# hid.net
KiCad netlist of a schematic drawn in EAGLE
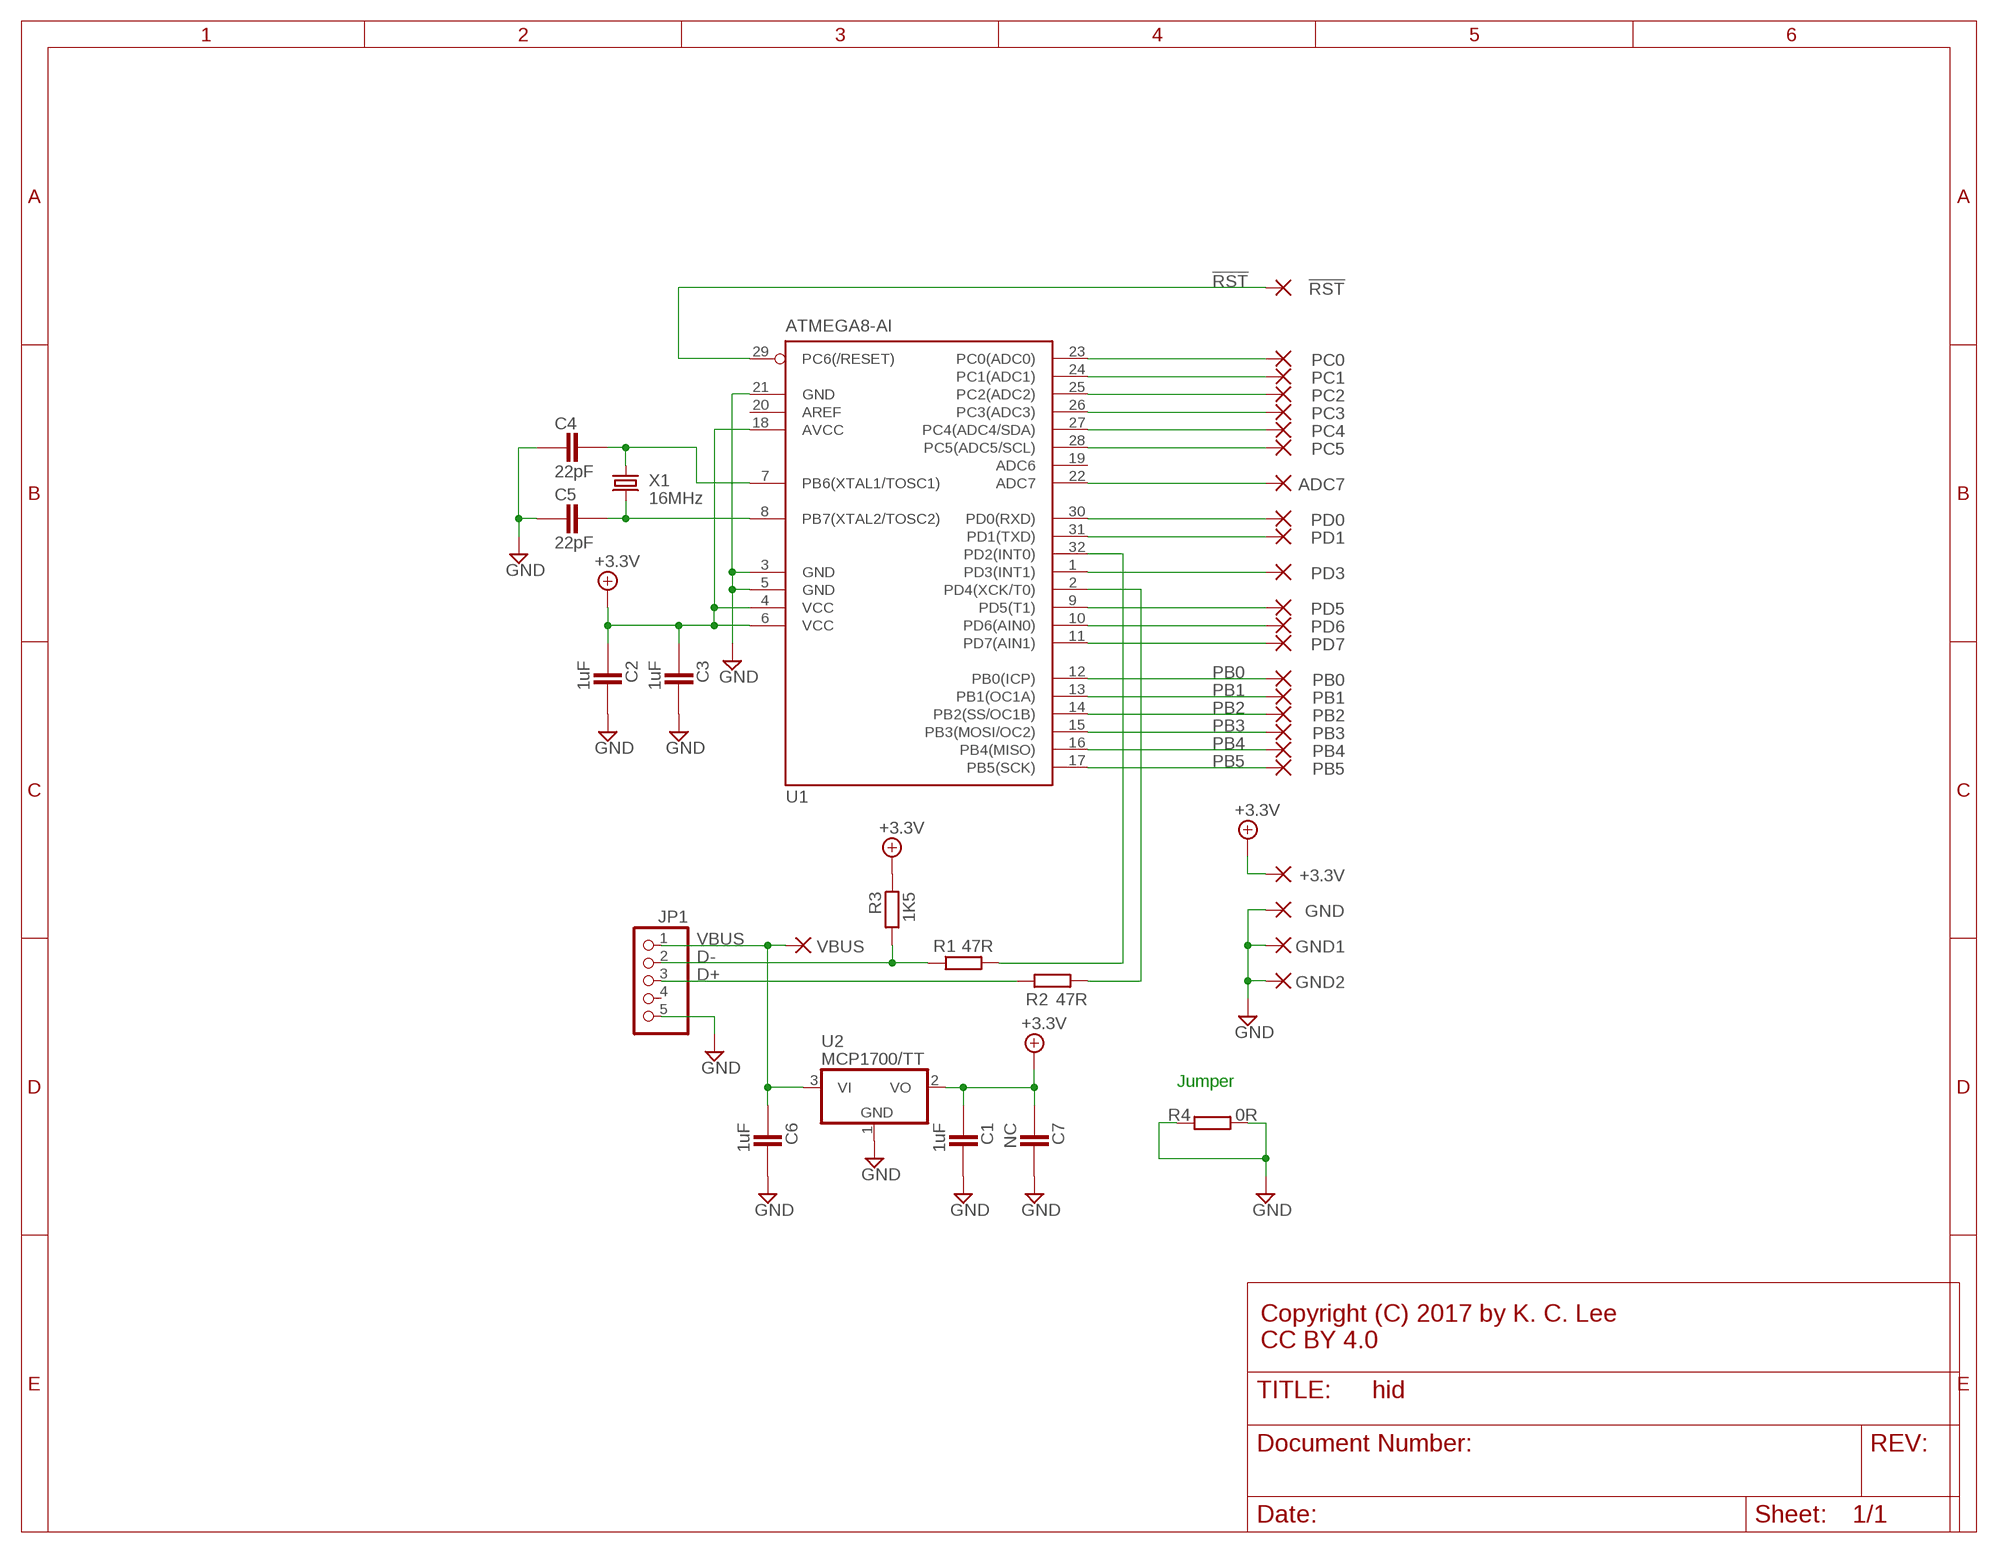
[diagram p0: schematic, sheet 1]

(export (version "E")
  (design (tool "Eeschema 10.0.6"))
  (components
    (comp (ref "!RST")
      (value "SMD2")
      (footprint "eagle-import:SMD1,27-2,54")
      (fields (field (name "PARTNO") "Breakout"))
      (libsource (lib "eagle-import") (part "SMD2"))
    )
    (comp (ref "+3.3V")
      (value "SMD2")
      (footprint "eagle-import:SMD1,27-2,54")
      (fields (field (name "PARTNO") "Breakout"))
      (libsource (lib "eagle-import") (part "SMD2"))
    )
    (comp (ref "ADC7")
      (value "SMD2")
      (footprint "eagle-import:SMD1,27-2,54")
      (fields (field (name "PARTNO") "Breakout"))
      (libsource (lib "eagle-import") (part "SMD2"))
    )
    (comp (ref "C1")
      (value "1uF")
      (footprint "eagle-import:CAPC1608X92N")
      (fields (field (name "PARTNO") "1uF X7R 0603"))
      (libsource (lib "eagle-import") (part "CAPACITOR_0603"))
    )
    (comp (ref "C2")
      (value "1uF")
      (footprint "eagle-import:CAPC1608X92N")
      (fields (field (name "PARTNO") "1uF X7R 0603"))
      (libsource (lib "eagle-import") (part "CAPACITOR_0603"))
    )
    (comp (ref "C3")
      (value "1uF")
      (footprint "eagle-import:CAPC1608X92N")
      (fields (field (name "PARTNO") "1uF X7R 0603"))
      (libsource (lib "eagle-import") (part "CAPACITOR_0603"))
    )
    (comp (ref "C4")
      (value "22pF")
      (footprint "eagle-import:CAPC1608X92N")
      (fields (field (name "PARTNO") "22pF 0603"))
      (libsource (lib "eagle-import") (part "CAPACITOR_0603"))
    )
    (comp (ref "C5")
      (value "22pF")
      (footprint "eagle-import:CAPC1608X92N")
      (fields (field (name "PARTNO") "22pF 0603"))
      (libsource (lib "eagle-import") (part "CAPACITOR_0603"))
    )
    (comp (ref "C6")
      (value "1uF")
      (footprint "eagle-import:CAPC1608X92N")
      (fields (field (name "PARTNO") "1uF X7R 0603"))
      (libsource (lib "eagle-import") (part "CAPACITOR_0603"))
    )
    (comp (ref "C7")
      (value "NC")
      (footprint "eagle-import:CAPC2012X145AN")
      (fields (field (name "PARTNO") "NC 0805"))
      (libsource (lib "eagle-import") (part "CAPACITOR_0805"))
    )
    (comp (ref "GND")
      (value "SMD2")
      (footprint "eagle-import:SMD1,27-2,54")
      (fields (field (name "PARTNO") "Breakout"))
      (libsource (lib "eagle-import") (part "SMD2"))
    )
    (comp (ref "GND1")
      (value "SMD2")
      (footprint "eagle-import:SMD1,27-2,54")
      (fields (field (name "PARTNO") "Breakout"))
      (libsource (lib "eagle-import") (part "SMD2"))
    )
    (comp (ref "GND2")
      (value "SMD2")
      (footprint "eagle-import:SMD1,27-2,54")
      (fields (field (name "PARTNO") "Breakout"))
      (libsource (lib "eagle-import") (part "SMD2"))
    )
    (comp (ref "JP1")
      (value "PINHD-1X5_2.54")
      (footprint "eagle-import:1X05")
      (libsource (lib "eagle-import") (part "PINHD-1X5_2.54"))
    )
    (comp (ref "PB0")
      (value "SMD2")
      (footprint "eagle-import:SMD1,27-2,54")
      (fields (field (name "PARTNO") "Breakout"))
      (libsource (lib "eagle-import") (part "SMD2"))
    )
    (comp (ref "PB1")
      (value "SMD2")
      (footprint "eagle-import:SMD1,27-2,54")
      (fields (field (name "PARTNO") "Breakout"))
      (libsource (lib "eagle-import") (part "SMD2"))
    )
    (comp (ref "PB2")
      (value "SMD2")
      (footprint "eagle-import:SMD1,27-2,54")
      (fields (field (name "PARTNO") "Breakout"))
      (libsource (lib "eagle-import") (part "SMD2"))
    )
    (comp (ref "PB3")
      (value "SMD2")
      (footprint "eagle-import:SMD1,27-2,54")
      (fields (field (name "PARTNO") "Breakout"))
      (libsource (lib "eagle-import") (part "SMD2"))
    )
    (comp (ref "PB4")
      (value "SMD2")
      (footprint "eagle-import:SMD1,27-2,54")
      (fields (field (name "PARTNO") "Breakout"))
      (libsource (lib "eagle-import") (part "SMD2"))
    )
    (comp (ref "PB5")
      (value "SMD2")
      (footprint "eagle-import:SMD1,27-2,54")
      (fields (field (name "PARTNO") "Breakout"))
      (libsource (lib "eagle-import") (part "SMD2"))
    )
    (comp (ref "PC0")
      (value "SMD2")
      (footprint "eagle-import:SMD1,27-2,54")
      (fields (field (name "PARTNO") "Breakout"))
      (libsource (lib "eagle-import") (part "SMD2"))
    )
    (comp (ref "PC1")
      (value "SMD2")
      (footprint "eagle-import:SMD1,27-2,54")
      (fields (field (name "PARTNO") "Breakout"))
      (libsource (lib "eagle-import") (part "SMD2"))
    )
    (comp (ref "PC2")
      (value "SMD2")
      (footprint "eagle-import:SMD1,27-2,54")
      (fields (field (name "PARTNO") "Breakout"))
      (libsource (lib "eagle-import") (part "SMD2"))
    )
    (comp (ref "PC3")
      (value "SMD2")
      (footprint "eagle-import:SMD1,27-2,54")
      (fields (field (name "PARTNO") "Breakout"))
      (libsource (lib "eagle-import") (part "SMD2"))
    )
    (comp (ref "PC4")
      (value "SMD2")
      (footprint "eagle-import:SMD1,27-2,54")
      (fields (field (name "PARTNO") "Breakout"))
      (libsource (lib "eagle-import") (part "SMD2"))
    )
    (comp (ref "PC5")
      (value "SMD2")
      (footprint "eagle-import:SMD1,27-2,54")
      (fields (field (name "PARTNO") "Breakout"))
      (libsource (lib "eagle-import") (part "SMD2"))
    )
    (comp (ref "PD0")
      (value "SMD2")
      (footprint "eagle-import:SMD1,27-2,54")
      (fields (field (name "PARTNO") "Breakout"))
      (libsource (lib "eagle-import") (part "SMD2"))
    )
    (comp (ref "PD1")
      (value "SMD2")
      (footprint "eagle-import:SMD1,27-2,54")
      (fields (field (name "PARTNO") "Breakout"))
      (libsource (lib "eagle-import") (part "SMD2"))
    )
    (comp (ref "PD3")
      (value "SMD2")
      (footprint "eagle-import:SMD1,27-2,54")
      (fields (field (name "PARTNO") "Breakout"))
      (libsource (lib "eagle-import") (part "SMD2"))
    )
    (comp (ref "PD5")
      (value "SMD2")
      (footprint "eagle-import:SMD1,27-2,54")
      (fields (field (name "PARTNO") "Breakout"))
      (libsource (lib "eagle-import") (part "SMD2"))
    )
    (comp (ref "PD6")
      (value "SMD2")
      (footprint "eagle-import:SMD1,27-2,54")
      (fields (field (name "PARTNO") "Breakout"))
      (libsource (lib "eagle-import") (part "SMD2"))
    )
    (comp (ref "PD7")
      (value "SMD2")
      (footprint "eagle-import:SMD1,27-2,54")
      (fields (field (name "PARTNO") "Breakout"))
      (libsource (lib "eagle-import") (part "SMD2"))
    )
    (comp (ref "R1")
      (value "47R")
      (footprint "eagle-import:RESC1608X55N")
      (fields (field (name "PARTNO") "47R 0603"))
      (libsource (lib "eagle-import") (part "RESISTOR_0603"))
    )
    (comp (ref "R2")
      (value "47R")
      (footprint "eagle-import:RESC1608X55N")
      (fields (field (name "PARTNO") "47R 0603"))
      (libsource (lib "eagle-import") (part "RESISTOR_0603"))
    )
    (comp (ref "R3")
      (value "1K5")
      (footprint "eagle-import:RESC1608X55N")
      (fields (field (name "PARTNO") "1K5 0603"))
      (libsource (lib "eagle-import") (part "RESISTOR_0603"))
    )
    (comp (ref "R4")
      (value "0R")
      (footprint "eagle-import:RESC3115X70N")
      (fields (field (name "PARTNO") "0R 1206"))
      (libsource (lib "eagle-import") (part "RESISTOR_1206"))
    )
    (comp (ref "U1")
      (value "ATMEGA8-AI")
      (footprint "eagle-import:TQFP32-08")
      (fields (field (name "PARTNO") "ATmega8A-AU"))
      (libsource (lib "eagle-import") (part "MEGA8-AI"))
    )
    (comp (ref "U2")
      (value "MCP1700/TT")
      (footprint "eagle-import:SOT95P280X135-3N")
      (fields (field (name "PARTNO") "MCP1700T-3302E/TT"))
      (libsource (lib "eagle-import") (part "MCP1700/TT"))
    )
    (comp (ref "VBUS")
      (value "SMD2")
      (footprint "eagle-import:SMD1,27-2,54")
      (fields (field (name "PARTNO") "Breakout"))
      (libsource (lib "eagle-import") (part "SMD2"))
    )
    (comp (ref "X1")
      (value "16MHz")
      (footprint "eagle-import:TC26H")
      (fields (field (name "PARTNO") "16MHz Crystal TC26"))
      (libsource (lib "eagle-import") (part "CRYSTALTC26H"))
    )
  )
  (nets
    (net (code "1") (name "+3.3V") (class "Default")
      (node (ref "+3.3V") (pin "1") (pinfunction "P_1") (pintype "passive"))
      (node (ref "C1") (pin "1") (pinfunction "1_1") (pintype "passive"))
      (node (ref "C2") (pin "1") (pinfunction "1_1") (pintype "passive"))
      (node (ref "C3") (pin "1") (pinfunction "1_1") (pintype "passive"))
      (node (ref "C7") (pin "1") (pinfunction "1_1") (pintype "passive"))
      (node (ref "R3") (pin "1") (pinfunction "1_1") (pintype "passive"))
      (node (ref "U1") (pin "18") (pinfunction "AVCC_18") (pintype "power_in"))
      (node (ref "U1") (pin "4") (pinfunction "VCC_4") (pintype "power_in"))
      (node (ref "U1") (pin "6") (pinfunction "VCC_6") (pintype "power_in"))
      (node (ref "U2") (pin "2") (pinfunction "VO_2") (pintype "passive"))
    )
    (net (code "2") (name "/D+") (class "Default")
      (node (ref "JP1") (pin "3") (pinfunction "3_3") (pintype "passive"))
      (node (ref "R2") (pin "1") (pinfunction "1_1") (pintype "passive"))
    )
    (net (code "3") (name "/D-") (class "Default")
      (node (ref "JP1") (pin "2") (pinfunction "2_2") (pintype "passive"))
      (node (ref "R1") (pin "1") (pinfunction "1_1") (pintype "passive"))
      (node (ref "R3") (pin "2") (pinfunction "2_2") (pintype "passive"))
    )
    (net (code "4") (name "/PB0") (class "Default")
      (node (ref "PB0") (pin "1") (pinfunction "P_1") (pintype "passive"))
      (node (ref "U1") (pin "12") (pinfunction "PB0(ICP)_12") (pintype "bidirectional"))
    )
    (net (code "5") (name "/PB1") (class "Default")
      (node (ref "PB1") (pin "1") (pinfunction "P_1") (pintype "passive"))
      (node (ref "U1") (pin "13") (pinfunction "PB1(OC1A)_13") (pintype "bidirectional"))
    )
    (net (code "6") (name "/PB2") (class "Default")
      (node (ref "PB2") (pin "1") (pinfunction "P_1") (pintype "passive"))
      (node (ref "U1") (pin "14") (pinfunction "PB2(SS/OC1B)_14") (pintype "bidirectional"))
    )
    (net (code "7") (name "/PB3") (class "Default")
      (node (ref "PB3") (pin "1") (pinfunction "P_1") (pintype "passive"))
      (node (ref "U1") (pin "15") (pinfunction "PB3(MOSI/OC2)_15") (pintype "bidirectional"))
    )
    (net (code "8") (name "/PB4") (class "Default")
      (node (ref "PB4") (pin "1") (pinfunction "P_1") (pintype "passive"))
      (node (ref "U1") (pin "16") (pinfunction "PB4(MISO)_16") (pintype "bidirectional"))
    )
    (net (code "9") (name "/PB5") (class "Default")
      (node (ref "PB5") (pin "1") (pinfunction "P_1") (pintype "passive"))
      (node (ref "U1") (pin "17") (pinfunction "PB5(SCK)_17") (pintype "bidirectional"))
    )
    (net (code "10") (name "/VBUS") (class "Default")
      (node (ref "C6") (pin "1") (pinfunction "1_1") (pintype "passive"))
      (node (ref "JP1") (pin "1") (pinfunction "1_1") (pintype "passive"))
      (node (ref "U2") (pin "3") (pinfunction "VI_3") (pintype "input"))
      (node (ref "VBUS") (pin "1") (pinfunction "P_1") (pintype "passive"))
    )
    (net (code "11") (name "/~{RST}") (class "Default")
      (node (ref "!RST") (pin "1") (pinfunction "P_1") (pintype "passive"))
      (node (ref "U1") (pin "29") (pinfunction "PC6(/RESET)_29") (pintype "bidirectional"))
    )
    (net (code "12") (name "GND") (class "Default")
      (node (ref "C1") (pin "2") (pinfunction "2_2") (pintype "passive"))
      (node (ref "C2") (pin "2") (pinfunction "2_2") (pintype "passive"))
      (node (ref "C3") (pin "2") (pinfunction "2_2") (pintype "passive"))
      (node (ref "C4") (pin "1") (pinfunction "1_1") (pintype "passive"))
      (node (ref "C5") (pin "1") (pinfunction "1_1") (pintype "passive"))
      (node (ref "C6") (pin "2") (pinfunction "2_2") (pintype "passive"))
      (node (ref "C7") (pin "2") (pinfunction "2_2") (pintype "passive"))
      (node (ref "GND") (pin "1") (pinfunction "P_1") (pintype "passive"))
      (node (ref "GND1") (pin "1") (pinfunction "P_1") (pintype "passive"))
      (node (ref "GND2") (pin "1") (pinfunction "P_1") (pintype "passive"))
      (node (ref "JP1") (pin "5") (pinfunction "5_5") (pintype "passive"))
      (node (ref "R4") (pin "1") (pinfunction "1_1") (pintype "passive"))
      (node (ref "R4") (pin "2") (pinfunction "2_2") (pintype "passive"))
      (node (ref "U1") (pin "21") (pinfunction "GND_21") (pintype "power_in"))
      (node (ref "U1") (pin "3") (pinfunction "GND_3") (pintype "power_in"))
      (node (ref "U1") (pin "5") (pinfunction "GND_5") (pintype "power_in"))
      (node (ref "U2") (pin "1") (pinfunction "GND_1") (pintype "passive"))
    )
    (net (code "13") (name "Net-(ADC7-P)") (class "Default")
      (node (ref "ADC7") (pin "1") (pinfunction "P_1") (pintype "passive"))
      (node (ref "U1") (pin "22") (pinfunction "ADC7_22") (pintype "bidirectional"))
    )
    (net (code "14") (name "Net-(PC0-P)") (class "Default")
      (node (ref "PC0") (pin "1") (pinfunction "P_1") (pintype "passive"))
      (node (ref "U1") (pin "23") (pinfunction "PC0(ADC0)_23") (pintype "bidirectional"))
    )
    (net (code "15") (name "Net-(PC1-P)") (class "Default")
      (node (ref "PC1") (pin "1") (pinfunction "P_1") (pintype "passive"))
      (node (ref "U1") (pin "24") (pinfunction "PC1(ADC1)_24") (pintype "bidirectional"))
    )
    (net (code "16") (name "Net-(PC2-P)") (class "Default")
      (node (ref "PC2") (pin "1") (pinfunction "P_1") (pintype "passive"))
      (node (ref "U1") (pin "25") (pinfunction "PC2(ADC2)_25") (pintype "bidirectional"))
    )
    (net (code "17") (name "Net-(PC3-P)") (class "Default")
      (node (ref "PC3") (pin "1") (pinfunction "P_1") (pintype "passive"))
      (node (ref "U1") (pin "26") (pinfunction "PC3(ADC3)_26") (pintype "bidirectional"))
    )
    (net (code "18") (name "Net-(PC4-P)") (class "Default")
      (node (ref "PC4") (pin "1") (pinfunction "P_1") (pintype "passive"))
      (node (ref "U1") (pin "27") (pinfunction "PC4(ADC4/SDA)_27") (pintype "bidirectional"))
    )
    (net (code "19") (name "Net-(PC5-P)") (class "Default")
      (node (ref "PC5") (pin "1") (pinfunction "P_1") (pintype "passive"))
      (node (ref "U1") (pin "28") (pinfunction "PC5(ADC5/SCL)_28") (pintype "bidirectional"))
    )
    (net (code "20") (name "Net-(PD0-P)") (class "Default")
      (node (ref "PD0") (pin "1") (pinfunction "P_1") (pintype "passive"))
      (node (ref "U1") (pin "30") (pinfunction "PD0(RXD)_30") (pintype "bidirectional"))
    )
    (net (code "21") (name "Net-(PD1-P)") (class "Default")
      (node (ref "PD1") (pin "1") (pinfunction "P_1") (pintype "passive"))
      (node (ref "U1") (pin "31") (pinfunction "PD1(TXD)_31") (pintype "bidirectional"))
    )
    (net (code "22") (name "Net-(PD3-P)") (class "Default")
      (node (ref "PD3") (pin "1") (pinfunction "P_1") (pintype "passive"))
      (node (ref "U1") (pin "1") (pinfunction "PD3(INT1)_1") (pintype "bidirectional"))
    )
    (net (code "23") (name "Net-(PD5-P)") (class "Default")
      (node (ref "PD5") (pin "1") (pinfunction "P_1") (pintype "passive"))
      (node (ref "U1") (pin "9") (pinfunction "PD5(T1)_9") (pintype "bidirectional"))
    )
    (net (code "24") (name "Net-(PD6-P)") (class "Default")
      (node (ref "PD6") (pin "1") (pinfunction "P_1") (pintype "passive"))
      (node (ref "U1") (pin "10") (pinfunction "PD6(AIN0)_10") (pintype "bidirectional"))
    )
    (net (code "25") (name "Net-(PD7-P)") (class "Default")
      (node (ref "PD7") (pin "1") (pinfunction "P_1") (pintype "passive"))
      (node (ref "U1") (pin "11") (pinfunction "PD7(AIN1)_11") (pintype "bidirectional"))
    )
    (net (code "26") (name "Net-(U1-PB6(XTAL1{slash}TOSC1))") (class "Default")
      (node (ref "C4") (pin "2") (pinfunction "2_2") (pintype "passive"))
      (node (ref "U1") (pin "7") (pinfunction "PB6(XTAL1/TOSC1)_7") (pintype "bidirectional"))
      (node (ref "X1") (pin "1") (pinfunction "1_1") (pintype "passive"))
    )
    (net (code "27") (name "Net-(U1-PB7(XTAL2{slash}TOSC2))") (class "Default")
      (node (ref "C5") (pin "2") (pinfunction "2_2") (pintype "passive"))
      (node (ref "U1") (pin "8") (pinfunction "PB7(XTAL2/TOSC2)_8") (pintype "bidirectional"))
      (node (ref "X1") (pin "2") (pinfunction "2_2") (pintype "passive"))
    )
    (net (code "28") (name "Net-(U1-PD2(INT0))") (class "Default")
      (node (ref "R1") (pin "2") (pinfunction "2_2") (pintype "passive"))
      (node (ref "U1") (pin "32") (pinfunction "PD2(INT0)_32") (pintype "bidirectional"))
    )
    (net (code "29") (name "Net-(U1-PD4(XCK{slash}T0))") (class "Default")
      (node (ref "R2") (pin "2") (pinfunction "2_2") (pintype "passive"))
      (node (ref "U1") (pin "2") (pinfunction "PD4(XCK/T0)_2") (pintype "bidirectional"))
    )
    (net (code "30") (name "unconnected-(JP1-Pad4)") (class "Default")
      (node (ref "JP1") (pin "4") (pinfunction "4_4") (pintype "passive"))
    )
    (net (code "31") (name "unconnected-(U1-ADC6-Pad19)") (class "Default")
      (node (ref "U1") (pin "19") (pinfunction "ADC6_19") (pintype "bidirectional"))
    )
    (net (code "32") (name "unconnected-(U1-AREF-Pad20)") (class "Default")
      (node (ref "U1") (pin "20") (pinfunction "AREF_20") (pintype "passive"))
    )
  )
)
